# MPCIE.net
KiCad netlist of a schematic drawn in Altium Designer
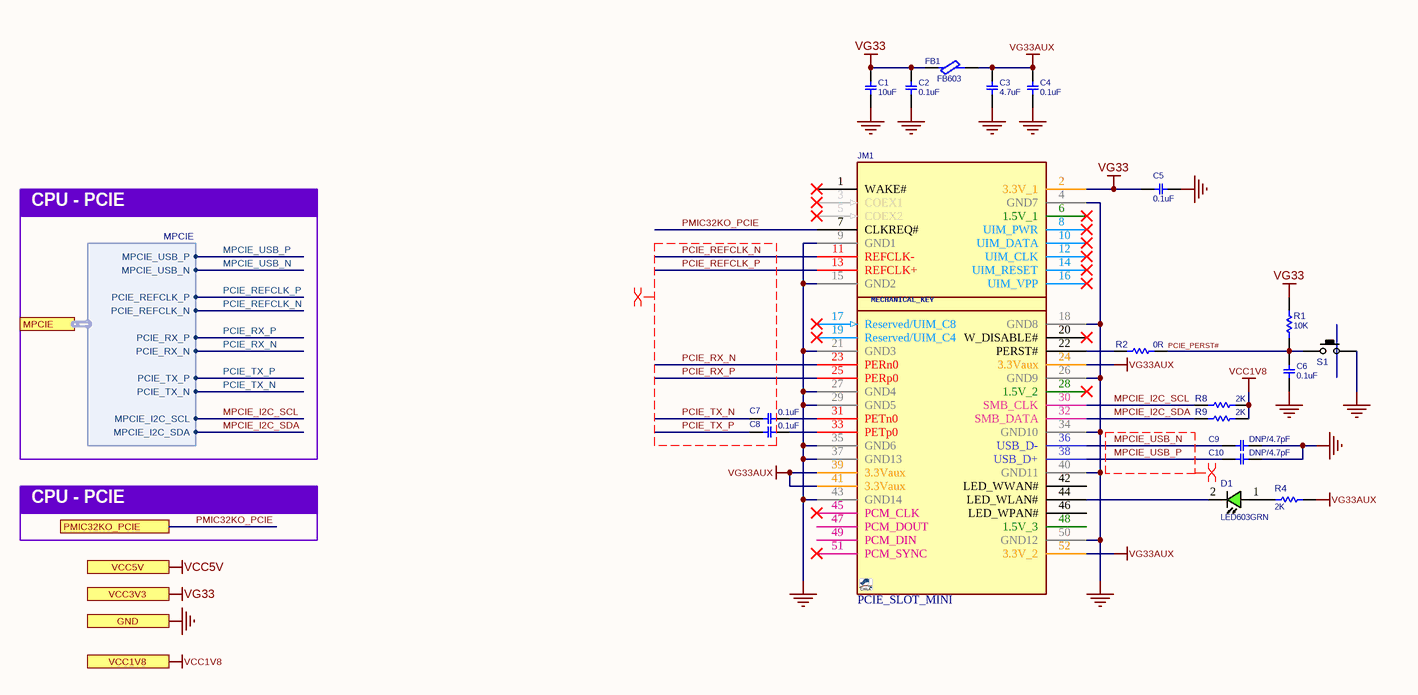
[diagram p0: MPCIE.SchDoc]

(export (version "E")
  (design (tool "Eeschema 10.0.6"))
  (components
    (comp (ref "C1")
      (value "10uF")
      (footprint "C0402")
      (description "CAP, MLCC")
      (fields (field (name "MANF_P#") "CL05A106MP5NUNC") (field (name "MANF") "Samsung"))
      (libsource (lib "mlcc_smd_passive") (part "CAP_SMD_MLCC"))
    )
    (comp (ref "C2")
      (value "0.1uF")
      (footprint "C0402")
      (description "CAP, MLCC")
      (fields (field (name "MANF_P#") "GRM155R61E104") (field (name "MANF") "Murata"))
      (libsource (lib "mlcc_smd_passive") (part "CAP_SMD_MLCC_100n50TDK"))
    )
    (comp (ref "C3")
      (value "4.7uF")
      (footprint "C0402")
      (description "CAP, MLCC")
      (fields (field (name "MANF_P#") "CL05A475MP5NRNC") (field (name "MANF") "Samsung"))
      (libsource (lib "passive_smd") (part "CAP_SMD_MLCC"))
    )
    (comp (ref "C4")
      (value "0.1uF")
      (footprint "C0402")
      (description "CAP, MLCC")
      (fields (field (name "MANF_P#") "GRM155R61E104") (field (name "MANF") "Murata"))
      (libsource (lib "mlcc_smd_passive") (part "CAP_SMD_MLCC_100n50TDK"))
    )
    (comp (ref "C5")
      (value "0.1uF")
      (footprint "C0402")
      (description "CAP, MLCC")
      (fields (field (name "MANF_P#") "GRM155R61E104") (field (name "MANF") "Murata"))
      (libsource (lib "mlcc_smd_passive") (part "CAP_SMD_MLCC_100n50TDK"))
    )
    (comp (ref "C6")
      (value "0.1uF")
      (footprint "C0402")
      (description "CAP, MLCC")
      (fields (field (name "MANF_P#") "GRM155R61E104") (field (name "MANF") "Murata"))
      (libsource (lib "mlcc_smd_passive") (part "CAP_SMD_MLCC_100n50TDK"))
    )
    (comp (ref "C7")
      (value "0.1uF")
      (footprint "C0402")
      (description "CAP, MLCC")
      (fields (field (name "MANF_P#") "GRM155R61E104") (field (name "MANF") "Murata"))
      (libsource (lib "mlcc_smd_passive") (part "CAP_SMD_MLCC_100n50TDK"))
    )
    (comp (ref "C8")
      (value "0.1uF")
      (footprint "C0402")
      (description "CAP, MLCC")
      (fields (field (name "MANF_P#") "GRM155R61E104") (field (name "MANF") "Murata"))
      (libsource (lib "mlcc_smd_passive") (part "CAP_SMD_MLCC_100n50TDK"))
    )
    (comp (ref "C9")
      (value "DNP/4.7pF")
      (footprint "C0402")
      (description "CAP, MLCC, 100nF, 50V, X7R, 10%, 0402C")
      (fields (field (name "MANF_P#") "GCM155R71H104KE02D") (field (name "MANF") "Murata"))
      (libsource (lib "mlcc_smd_passive") (part "CAP_SMD_MLCC_100n50TDK"))
    )
    (comp (ref "C10")
      (value "DNP/4.7pF")
      (footprint "C0402")
      (description "CAP, MLCC, 100nF, 50V, X7R, 10%, 0402C")
      (fields (field (name "MANF_P#") "GCM155R71H104KE02D") (field (name "MANF") "Murata"))
      (libsource (lib "mlcc_smd_passive") (part "CAP_SMD_MLCC_100n50TDK"))
    )
    (comp (ref "D1")
      (value "LED603GRN")
      (footprint "LED0603GRN")
      (description "LED, SMD, 0603, GREEN")
      (fields (field (name "MANF") "OSRAM") (field (name "MANF_P#") "LG Q396-PS-35"))
      (libsource (lib "led(diode)") (part "LED_SMD_0603_GRN_OSRAM"))
    )
    (comp (ref "FB1")
      (value "FB603")
      (footprint "L0603")
      (description "FERRITE_Bead, 0603, 1.3A, 150mOhm, 600@100MHz")
      (fields (field (name "MANF") "MURATA") (field (name "MANF_P#") "BLM18KG601SN1D"))
      (libsource (lib "emi_filter") (part "FBEAD_SMD_BLM18KG601"))
    )
    (comp (ref "JM1")
      (value "PCIE_SLOT_MINI")
      (footprint "PCIE_MIN_CARD_FULL")
      (description "CONN, PCIE SLOT, MINI, 2X26, SMT 0.8mm SP 1136H")
      (fields
        (field (name "MANF") "Molex, JAE Electronics")
        (field (name "MANF_P#") "679100002, MM60-52B1-E1-R650")
      )
      (libsource (lib "conn_pcie_pci") (part "PCIE_SLOT_MINI"))
    )
    (comp (ref "R1")
      (value "10K")
      (footprint "R0402")
      (description "RESISTOR, SMD")
      (libsource (lib "passive_res_smd") (part "RES_SMD"))
    )
    (comp (ref "R2")
      (value "0R")
      (footprint "R0402")
      (description "RESISTOR, SMD")
      (libsource (lib "passive_res_smd") (part "RES_SMD"))
    )
    (comp (ref "R4")
      (value "2K")
      (footprint "R0402")
      (description "RESISTOR, SMD")
      (libsource (lib "passive_res_smd") (part "RES_SMD"))
    )
    (comp (ref "R8")
      (value "2K")
      (footprint "R0402")
      (description "RESISTOR, SMD")
      (libsource (lib "passive_res_smd") (part "RES_SMD"))
    )
    (comp (ref "R9")
      (value "2K")
      (footprint "R0402")
      (description "RESISTOR, SMD")
      (libsource (lib "passive_res_smd") (part "RES_SMD"))
    )
    (comp (ref "S1")
      (value "PUSHBUTTON")
      (footprint "SWPBS_SPST_3X2X1")
      (description "SWITCH, PUSH BUTTON, TACTILE, SMD, SPST, 3X2.5X1.2mm")
      (fields (field (name "MANF") "OMRON") (field (name "MANF_P#") "B3U-1000P"))
      (libsource (lib "switch_tact_PUSHB") (part "SWPBS_SPST_3X2_B3U-1000P"))
    )
  )
  (nets
    (net (code "2") (name "/MPCIE_I2C_SCL") (class "Default")
      (node (ref "JM1") (pin "30") (pinfunction "SMB_CLK_30") (pintype "passive"))
      (node (ref "R8") (pin "1") (pinfunction "1_1") (pintype "passive"))
    )
    (net (code "3") (name "/MPCIE_I2C_SDA") (class "Default")
      (node (ref "JM1") (pin "32") (pinfunction "SMB_DATA_32") (pintype "passive"))
      (node (ref "R9") (pin "1") (pinfunction "1_1") (pintype "passive"))
    )
    (net (code "4") (name "/MPCIE_USB_N") (class "Default")
      (node (ref "C9") (pin "2") (pinfunction "2_2") (pintype "passive"))
      (node (ref "JM1") (pin "36") (pinfunction "USB_D-_36") (pintype "passive"))
    )
    (net (code "5") (name "/MPCIE_USB_P") (class "Default")
      (node (ref "C10") (pin "2") (pinfunction "2_2") (pintype "passive"))
      (node (ref "JM1") (pin "38") (pinfunction "USB_D+_38") (pintype "passive"))
    )
    (net (code "6") (name "/PCIE_PERST#") (class "Default")
      (node (ref "C6") (pin "2") (pinfunction "2_2") (pintype "passive"))
      (node (ref "R1") (pin "2") (pinfunction "2_2") (pintype "passive"))
      (node (ref "R2") (pin "2") (pinfunction "2_2") (pintype "passive"))
      (node (ref "S1") (pin "1") (pinfunction "P1_1") (pintype "passive"))
    )
    (net (code "7") (name "/PCIE_REFCLK_N") (class "Default")
      (node (ref "JM1") (pin "11") (pinfunction "REFCLK-_11") (pintype "passive"))
    )
    (net (code "8") (name "/PCIE_REFCLK_P") (class "Default")
      (node (ref "JM1") (pin "13") (pinfunction "REFCLK+_13") (pintype "passive"))
    )
    (net (code "9") (name "/PCIE_RX_N") (class "Default")
      (node (ref "JM1") (pin "23") (pinfunction "PERn0_23") (pintype "passive"))
    )
    (net (code "10") (name "/PCIE_RX_P") (class "Default")
      (node (ref "JM1") (pin "25") (pinfunction "PERp0_25") (pintype "passive"))
    )
    (net (code "11") (name "/PCIE_TX_N") (class "Default")
      (node (ref "C7") (pin "2") (pinfunction "2_2") (pintype "passive"))
    )
    (net (code "12") (name "/PCIE_TX_P") (class "Default")
      (node (ref "C8") (pin "2") (pinfunction "2_2") (pintype "passive"))
    )
    (net (code "13") (name "/PMIC32KO_PCIE") (class "Default")
      (node (ref "JM1") (pin "7") (pinfunction "CLKREQ#_7") (pintype "passive"))
    )
    (net (code "15") (name "GND") (class "Default")
      (node (ref "C1") (pin "2") (pinfunction "2_2") (pintype "passive"))
      (node (ref "C10") (pin "1") (pinfunction "1_1") (pintype "passive"))
      (node (ref "C2") (pin "2") (pinfunction "2_2") (pintype "passive"))
      (node (ref "C3") (pin "1") (pinfunction "1_1") (pintype "passive"))
      (node (ref "C4") (pin "2") (pinfunction "2_2") (pintype "passive"))
      (node (ref "C5") (pin "2") (pinfunction "2_2") (pintype "passive"))
      (node (ref "C6") (pin "1") (pinfunction "1_1") (pintype "passive"))
      (node (ref "C9") (pin "1") (pinfunction "1_1") (pintype "passive"))
      (node (ref "JM1") (pin "15") (pinfunction "GND2_15") (pintype "passive"))
      (node (ref "JM1") (pin "18") (pinfunction "GND8_18") (pintype "passive"))
      (node (ref "JM1") (pin "21") (pinfunction "GND3_21") (pintype "passive"))
      (node (ref "JM1") (pin "26") (pinfunction "GND9_26") (pintype "passive"))
      (node (ref "JM1") (pin "27") (pinfunction "GND4_27") (pintype "passive"))
      (node (ref "JM1") (pin "29") (pinfunction "GND5_29") (pintype "passive"))
      (node (ref "JM1") (pin "34") (pinfunction "GND10_34") (pintype "passive"))
      (node (ref "JM1") (pin "35") (pinfunction "GND6_35") (pintype "passive"))
      (node (ref "JM1") (pin "37") (pinfunction "GND13_37") (pintype "passive"))
      (node (ref "JM1") (pin "4") (pinfunction "GND7_4") (pintype "passive"))
      (node (ref "JM1") (pin "40") (pinfunction "GND11_40") (pintype "passive"))
      (node (ref "JM1") (pin "43") (pinfunction "GND14_43") (pintype "passive"))
      (node (ref "JM1") (pin "50") (pinfunction "GND12_50") (pintype "passive"))
      (node (ref "JM1") (pin "9") (pinfunction "GND1_9") (pintype "passive"))
      (node (ref "S1") (pin "2") (pinfunction "P3_2") (pintype "passive"))
    )
    (net (code "16") (name "Net-(D1-ANODE)") (class "Default")
      (node (ref "D1") (pin "1") (pinfunction "ANODE_1") (pintype "passive"))
      (node (ref "R4") (pin "1") (pinfunction "1_1") (pintype "passive"))
    )
    (net (code "17") (name "Net-(D1-CATHODE)") (class "Default")
      (node (ref "D1") (pin "2") (pinfunction "CATHODE_2") (pintype "passive"))
      (node (ref "JM1") (pin "44") (pinfunction "LED_WLAN#_44") (pintype "passive"))
    )
    (net (code "18") (name "Net-(JM1-PERST#)") (class "Default")
      (node (ref "JM1") (pin "22") (pinfunction "PERST#_22") (pintype "passive"))
      (node (ref "R2") (pin "1") (pinfunction "1_1") (pintype "passive"))
    )
    (net (code "19") (name "Net-(JM1-PETn0)") (class "Default")
      (node (ref "C7") (pin "1") (pinfunction "1_1") (pintype "passive"))
      (node (ref "JM1") (pin "31") (pinfunction "PETn0_31") (pintype "passive"))
    )
    (net (code "20") (name "Net-(JM1-PETp0)") (class "Default")
      (node (ref "C8") (pin "1") (pinfunction "1_1") (pintype "passive"))
      (node (ref "JM1") (pin "33") (pinfunction "PETp0_33") (pintype "passive"))
    )
    (net (code "21") (name "VCC1V8") (class "Default")
      (node (ref "R8") (pin "2") (pinfunction "2_2") (pintype "passive"))
      (node (ref "R9") (pin "2") (pinfunction "2_2") (pintype "passive"))
    )
    (net (code "23") (name "VG33") (class "Default")
      (node (ref "C1") (pin "1") (pinfunction "1_1") (pintype "passive"))
      (node (ref "C2") (pin "1") (pinfunction "1_1") (pintype "passive"))
      (node (ref "C5") (pin "1") (pinfunction "1_1") (pintype "passive"))
      (node (ref "FB1") (pin "1") (pinfunction "1_1") (pintype "passive"))
      (node (ref "JM1") (pin "2") (pinfunction "3.3V_1_2") (pintype "passive"))
      (node (ref "R1") (pin "1") (pinfunction "1_1") (pintype "passive"))
    )
    (net (code "24") (name "VG33AUX") (class "Default")
      (node (ref "C3") (pin "2") (pinfunction "2_2") (pintype "passive"))
      (node (ref "C4") (pin "1") (pinfunction "1_1") (pintype "passive"))
      (node (ref "FB1") (pin "2") (pinfunction "2_2") (pintype "passive"))
      (node (ref "JM1") (pin "24") (pinfunction "3.3Vaux_24") (pintype "passive"))
      (node (ref "JM1") (pin "39") (pinfunction "3.3Vaux_39") (pintype "passive"))
      (node (ref "JM1") (pin "41") (pinfunction "3.3Vaux_41") (pintype "passive"))
      (node (ref "JM1") (pin "52") (pinfunction "3.3V_2_52") (pintype "passive"))
      (node (ref "R4") (pin "2") (pinfunction "2_2") (pintype "passive"))
    )
    (net (code "25") (name "unconnected-(JM1-1.5V_1-Pad6)") (class "Default")
      (node (ref "JM1") (pin "6") (pinfunction "1.5V_1_6") (pintype "passive+no_connect"))
    )
    (net (code "26") (name "unconnected-(JM1-1.5V_2-Pad28)") (class "Default")
      (node (ref "JM1") (pin "28") (pinfunction "1.5V_2_28") (pintype "passive+no_connect"))
    )
    (net (code "27") (name "unconnected-(JM1-1.5V_3-Pad48)") (class "Default")
      (node (ref "JM1") (pin "48") (pinfunction "1.5V_3_48") (pintype "passive"))
    )
    (net (code "28") (name "unconnected-(JM1-COEX1-Pad3)") (class "Default")
      (node (ref "JM1") (pin "3") (pinfunction "COEX1_3") (pintype "input+no_connect"))
    )
    (net (code "29") (name "unconnected-(JM1-COEX2-Pad5)") (class "Default")
      (node (ref "JM1") (pin "5") (pinfunction "COEX2_5") (pintype "input+no_connect"))
    )
    (net (code "30") (name "unconnected-(JM1-LED_WPAN#-Pad46)") (class "Default")
      (node (ref "JM1") (pin "46") (pinfunction "LED_WPAN#_46") (pintype "passive"))
    )
    (net (code "31") (name "unconnected-(JM1-LED_WWAN#-Pad42)") (class "Default")
      (node (ref "JM1") (pin "42") (pinfunction "LED_WWAN#_42") (pintype "passive"))
    )
    (net (code "32") (name "unconnected-(JM1-PCM_CLK-Pad45)") (class "Default")
      (node (ref "JM1") (pin "45") (pinfunction "PCM_CLK_45") (pintype "passive+no_connect"))
    )
    (net (code "33") (name "unconnected-(JM1-PCM_DIN-Pad49)") (class "Default")
      (node (ref "JM1") (pin "49") (pinfunction "PCM_DIN_49") (pintype "passive"))
    )
    (net (code "34") (name "unconnected-(JM1-PCM_DOUT-Pad47)") (class "Default")
      (node (ref "JM1") (pin "47") (pinfunction "PCM_DOUT_47") (pintype "passive"))
    )
    (net (code "35") (name "unconnected-(JM1-PCM_SYNC-Pad51)") (class "Default")
      (node (ref "JM1") (pin "51") (pinfunction "PCM_SYNC_51") (pintype "passive+no_connect"))
    )
    (net (code "36") (name "unconnected-(JM1-Reserved{slash}UIM_C4-Pad19)") (class "Default")
      (node (ref "JM1") (pin "19") (pinfunction "Reserved/UIM_C4_19") (pintype "passive+no_connect"))
    )
    (net (code "37") (name "unconnected-(JM1-Reserved{slash}UIM_C8-Pad17)") (class "Default")
      (node (ref "JM1") (pin "17") (pinfunction "Reserved/UIM_C8_17") (pintype "input+no_connect"))
    )
    (net (code "38") (name "unconnected-(JM1-UIM_CLK-Pad12)") (class "Default")
      (node (ref "JM1") (pin "12") (pinfunction "UIM_CLK_12") (pintype "passive+no_connect"))
    )
    (net (code "39") (name "unconnected-(JM1-UIM_DATA-Pad10)") (class "Default")
      (node (ref "JM1") (pin "10") (pinfunction "UIM_DATA_10") (pintype "passive+no_connect"))
    )
    (net (code "40") (name "unconnected-(JM1-UIM_PWR-Pad8)") (class "Default")
      (node (ref "JM1") (pin "8") (pinfunction "UIM_PWR_8") (pintype "passive+no_connect"))
    )
    (net (code "41") (name "unconnected-(JM1-UIM_RESET-Pad14)") (class "Default")
      (node (ref "JM1") (pin "14") (pinfunction "UIM_RESET_14") (pintype "passive+no_connect"))
    )
    (net (code "42") (name "unconnected-(JM1-UIM_VPP-Pad16)") (class "Default")
      (node (ref "JM1") (pin "16") (pinfunction "UIM_VPP_16") (pintype "passive+no_connect"))
    )
    (net (code "43") (name "unconnected-(JM1-WAKE#-Pad1)") (class "Default")
      (node (ref "JM1") (pin "1") (pinfunction "WAKE#_1") (pintype "passive+no_connect"))
    )
    (net (code "44") (name "unconnected-(JM1-W_DISABLE#-Pad20)") (class "Default")
      (node (ref "JM1") (pin "20") (pinfunction "W_DISABLE#_20") (pintype "passive+no_connect"))
    )
  )
)
